# 6coils.net
KiCad netlist of a schematic drawn in EasyEDA
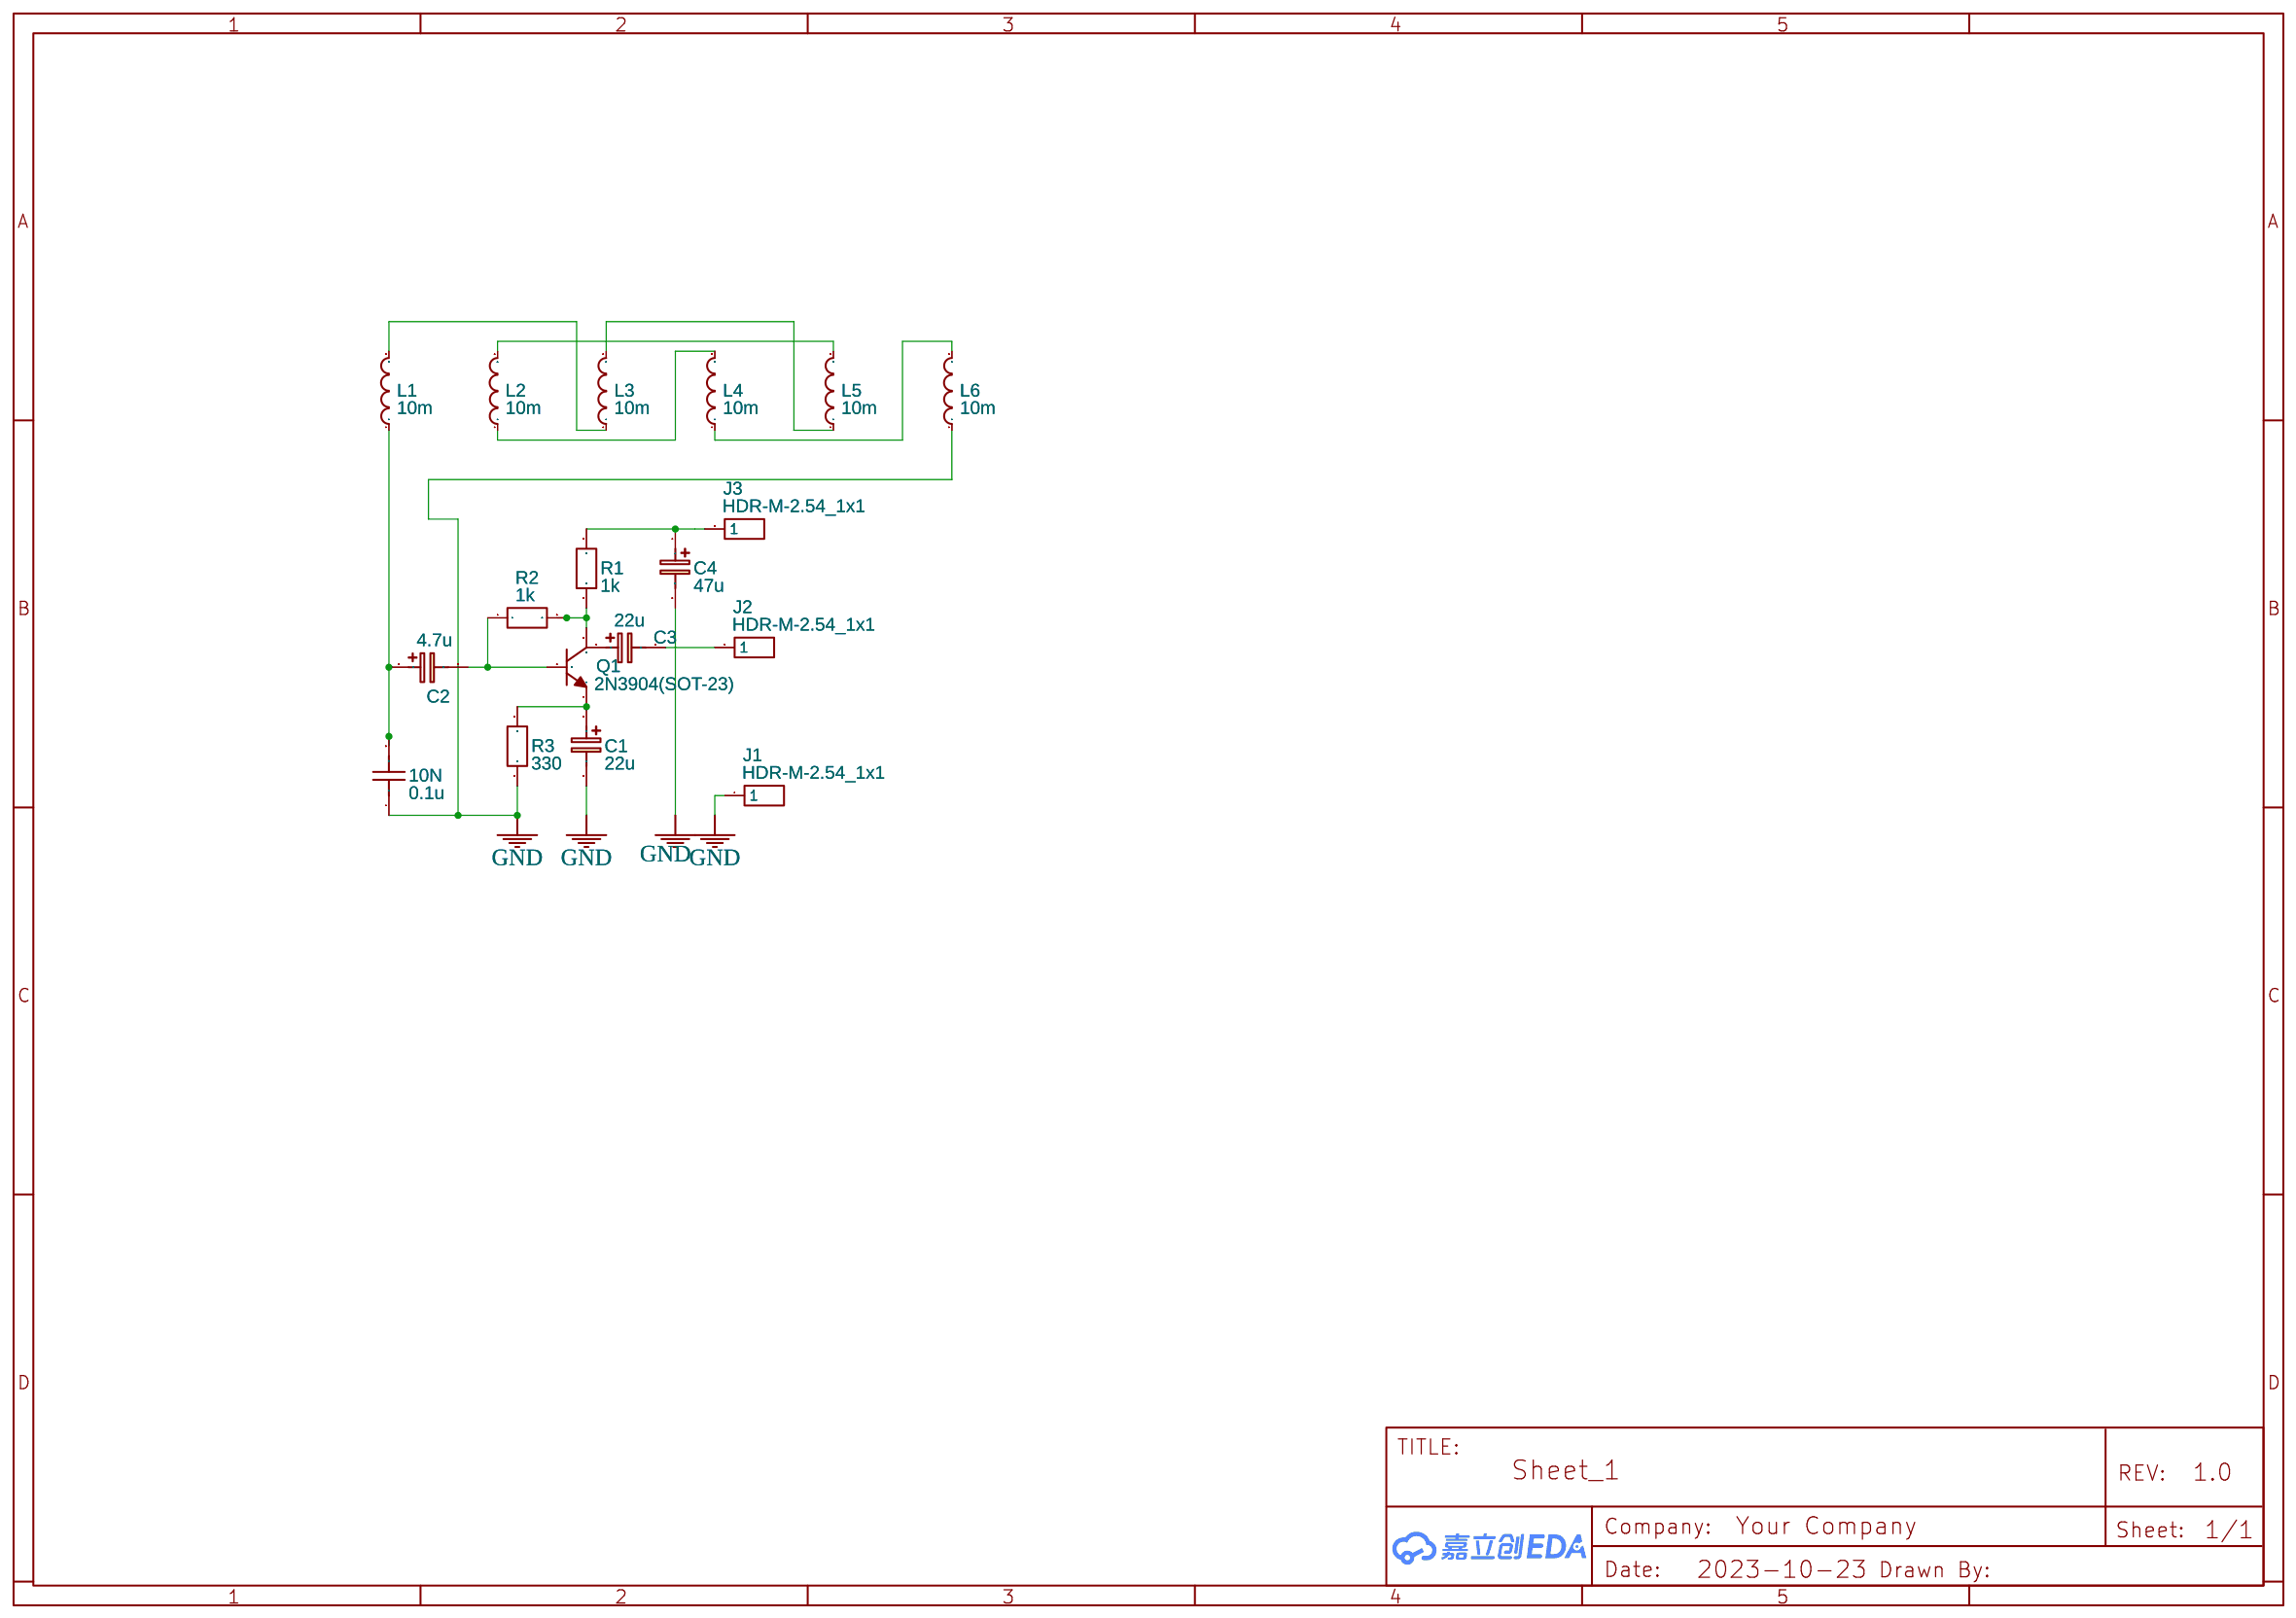
[diagram p0: schematic sheet]

(export (version "E")
  (design (tool "Eeschema 10.0.6"))
  (components
    (comp (ref "10N") (value "0.1u") (libsource (lib "") (part "C_0603_US")))
    (comp (ref "C1") (value "22u") (libsource (lib "") (part "C_Tan_SMD_A_EU")))
    (comp (ref "C2") (value "4.7u") (libsource (lib "") (part "C_Tan_SMD_A_EU_3")))
    (comp (ref "C3") (value "22u") (libsource (lib "") (part "C_Tan_SMD_A_EU_1")))
    (comp (ref "C4") (value "47u") (libsource (lib "") (part "C_Tan_SMD_A_EU_2")))
    (comp (ref "J1")
      (value "HDR-M-2.54_1x1")
      (fields (field (name "BOM_Supplier Part") "C81276"))
      (libsource (lib "") (part "HDR-M-2.54_1x1"))
    )
    (comp (ref "J2")
      (value "HDR-M-2.54_1x1")
      (fields (field (name "BOM_Supplier Part") "C81276"))
      (libsource (lib "") (part "HDR-M-2.54_1x1"))
    )
    (comp (ref "J3")
      (value "HDR-M-2.54_1x1")
      (fields (field (name "BOM_Supplier Part") "C81276"))
      (libsource (lib "") (part "HDR-M-2.54_1x1"))
    )
    (comp (ref "L1") (value "10m") (libsource (lib "") (part "L0603_US")))
    (comp (ref "L2") (value "10m") (libsource (lib "") (part "L0603_US")))
    (comp (ref "L3") (value "10m") (libsource (lib "") (part "L0603_US")))
    (comp (ref "L4") (value "10m") (libsource (lib "") (part "L0603_US")))
    (comp (ref "L5") (value "10m") (libsource (lib "") (part "L0603_US")))
    (comp (ref "L6") (value "10m") (libsource (lib "") (part "L0603_US")))
    (comp (ref "Q1")
      (value "2N3904(SOT-23)")
      (fields
        (field (name "BOM_Manufacturer Part") "2n3904S-RTK/PS")
        (field (name "BOM_Supplier Part") "C18536")
      )
      (libsource (lib "") (part "2N3904(SOT-23)"))
    )
    (comp (ref "R1") (value "1k") (libsource (lib "") (part "R_0603_EU")))
    (comp (ref "R2") (value "1k") (libsource (lib "") (part "R_0603_EU_1")))
    (comp (ref "R3") (value "330") (libsource (lib "") (part "R_0603_EU")))
  )
  (nets
    (net (code "1") (name "GND") (class "Default")
      (node (ref "10N") (pin "1") (pinfunction "1_1") (pintype "unspecified"))
      (node (ref "C1") (pin "2") (pinfunction "2_2") (pintype "unspecified"))
      (node (ref "C4") (pin "2") (pinfunction "2_2") (pintype "unspecified"))
      (node (ref "J1") (pin "1") (pinfunction "1_1") (pintype "input"))
      (node (ref "L6") (pin "1") (pinfunction "1_1") (pintype "unspecified"))
      (node (ref "R3") (pin "1") (pinfunction "1_1") (pintype "unspecified"))
    )
    (net (code "2") (name "Net-(10N-Pad2)") (class "Default")
      (node (ref "10N") (pin "2") (pinfunction "2_2") (pintype "unspecified"))
      (node (ref "C2") (pin "1") (pinfunction "1_1") (pintype "unspecified"))
      (node (ref "L1") (pin "1") (pinfunction "1_1") (pintype "unspecified"))
    )
    (net (code "3") (name "Net-(C3-Pad2)") (class "Default")
      (node (ref "C3") (pin "2") (pinfunction "2_2") (pintype "unspecified"))
      (node (ref "J2") (pin "1") (pinfunction "1_1") (pintype "input"))
    )
    (net (code "4") (name "Net-(C4-Pad1)") (class "Default")
      (node (ref "C4") (pin "1") (pinfunction "1_1") (pintype "unspecified"))
      (node (ref "J3") (pin "1") (pinfunction "1_1") (pintype "input"))
      (node (ref "R1") (pin "2") (pinfunction "2_2") (pintype "unspecified"))
    )
    (net (code "5") (name "Net-(L1-Pad2)") (class "Default")
      (node (ref "L1") (pin "2") (pinfunction "2_2") (pintype "unspecified"))
      (node (ref "L3") (pin "1") (pinfunction "1_1") (pintype "unspecified"))
    )
    (net (code "6") (name "Net-(L2-Pad1)") (class "Default")
      (node (ref "L2") (pin "1") (pinfunction "1_1") (pintype "unspecified"))
      (node (ref "L4") (pin "2") (pinfunction "2_2") (pintype "unspecified"))
    )
    (net (code "7") (name "Net-(L2-Pad2)") (class "Default")
      (node (ref "L2") (pin "2") (pinfunction "2_2") (pintype "unspecified"))
      (node (ref "L5") (pin "2") (pinfunction "2_2") (pintype "unspecified"))
    )
    (net (code "8") (name "Net-(L3-Pad2)") (class "Default")
      (node (ref "L3") (pin "2") (pinfunction "2_2") (pintype "unspecified"))
      (node (ref "L5") (pin "1") (pinfunction "1_1") (pintype "unspecified"))
    )
    (net (code "9") (name "Net-(L4-Pad1)") (class "Default")
      (node (ref "L4") (pin "1") (pinfunction "1_1") (pintype "unspecified"))
      (node (ref "L6") (pin "2") (pinfunction "2_2") (pintype "unspecified"))
    )
    (net (code "10") (name "Net-(Q1-B)") (class "Default")
      (node (ref "C2") (pin "2") (pinfunction "2_2") (pintype "unspecified"))
      (node (ref "Q1") (pin "2") (pinfunction "B_2") (pintype "input"))
      (node (ref "R2") (pin "1") (pinfunction "1_1") (pintype "unspecified"))
    )
    (net (code "11") (name "Net-(Q1-C)") (class "Default")
      (node (ref "Q1") (pin "3") (pinfunction "C_3") (pintype "input"))
      (node (ref "R1") (pin "1") (pinfunction "1_1") (pintype "unspecified"))
      (node (ref "R2") (pin "2") (pinfunction "2_2") (pintype "unspecified"))
    )
    (net (code "12") (name "Net-(Q1-E)") (class "Default")
      (node (ref "C1") (pin "1") (pinfunction "1_1") (pintype "unspecified"))
      (node (ref "Q1") (pin "1") (pinfunction "E_1") (pintype "input"))
      (node (ref "R3") (pin "2") (pinfunction "2_2") (pintype "unspecified"))
    )
    (net (code "13") (name "unconnected-(C3-Pad1)") (class "Default")
      (node (ref "C3") (pin "1") (pinfunction "1_1") (pintype "unspecified"))
    )
  )
)
